# Qwiic_UV_Sensor_VEML6075.net
KiCad netlist of a schematic drawn in EAGLE
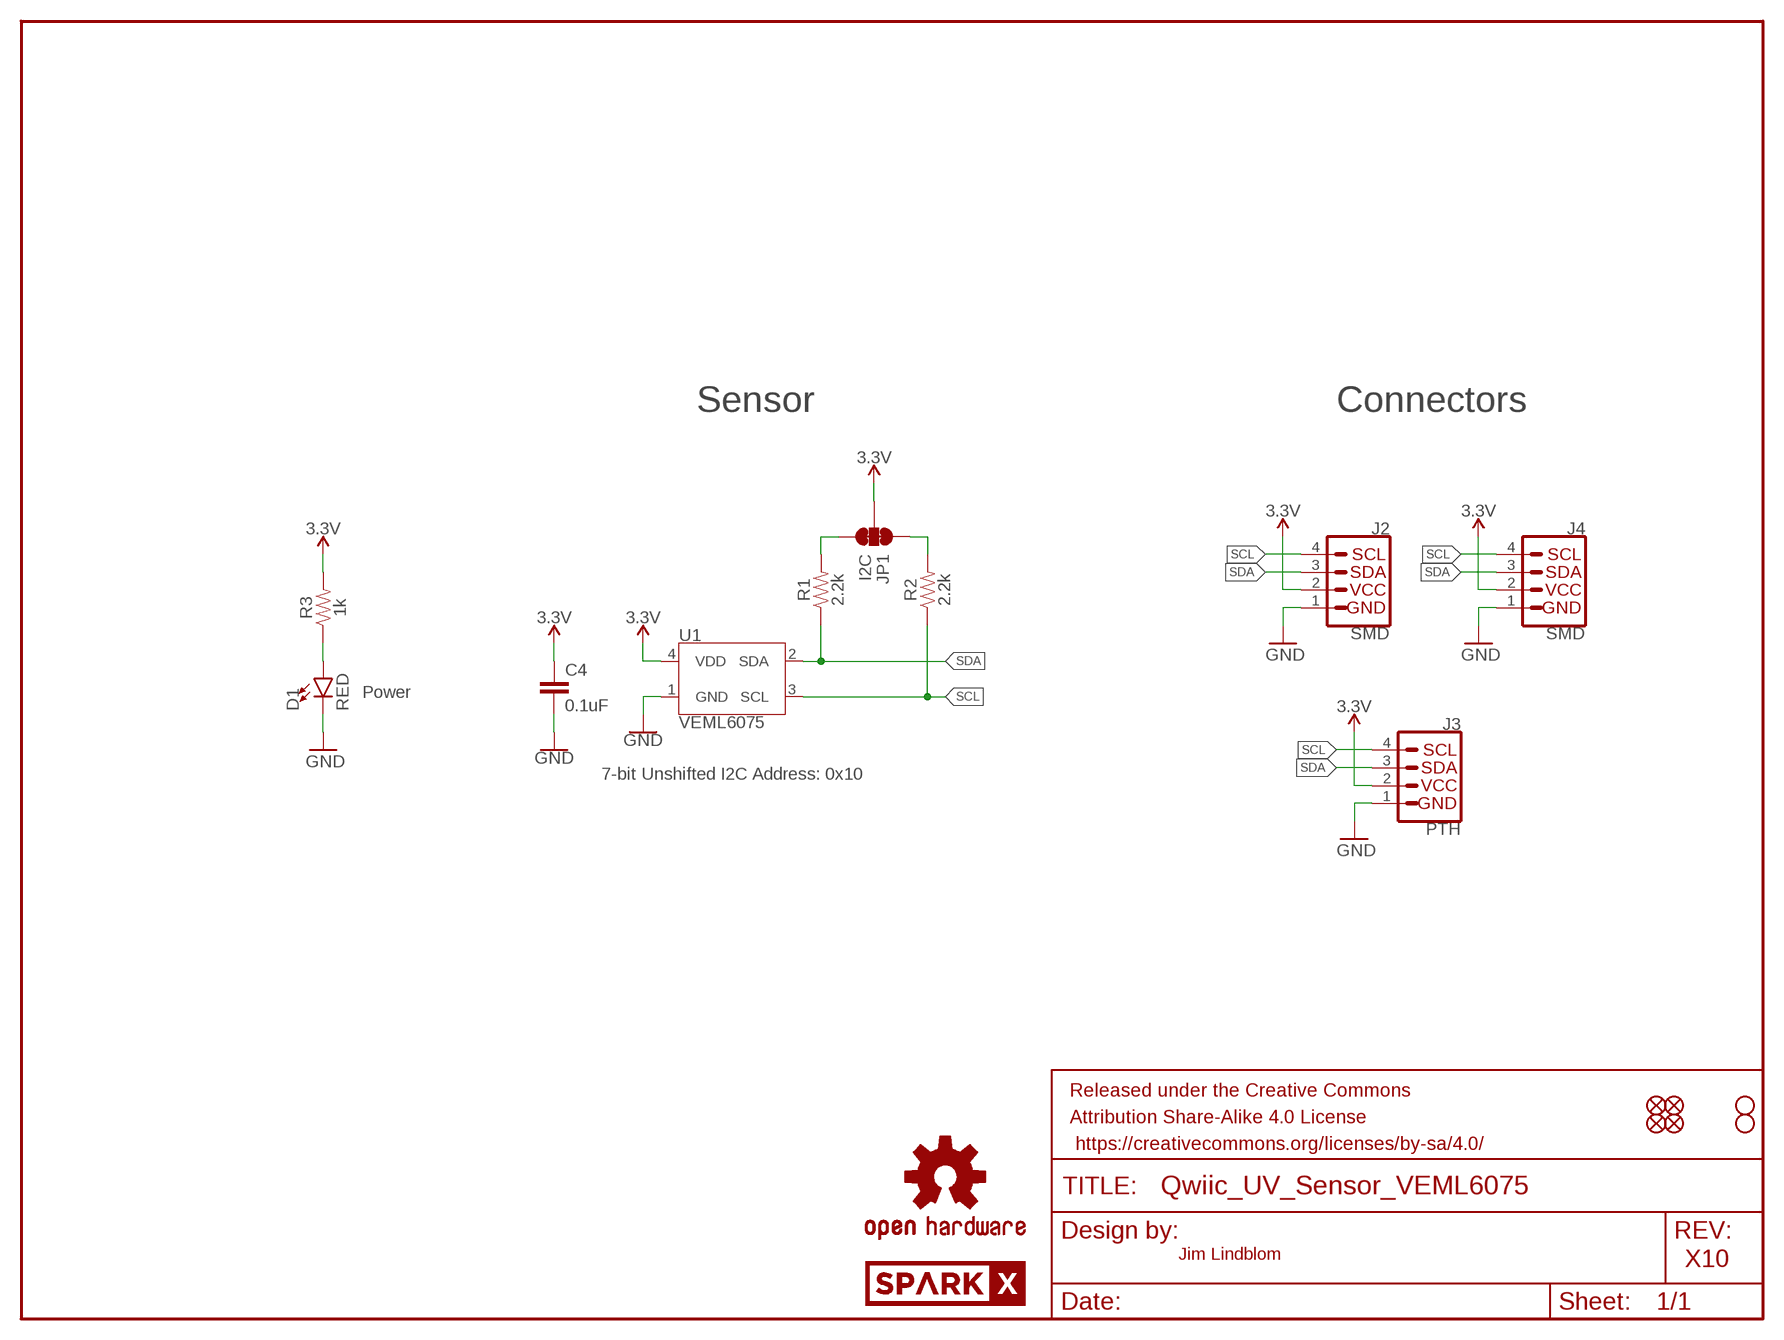
[diagram p0: schematic, sheet 1]

(export (version "E")
  (design (tool "Eeschema 10.0.6"))
  (components
    (comp (ref "C4")
      (value "0.1uF")
      (footprint "eagle-import:0603")
      (libsource (lib "eagle-import") (part "0.1UF-0603-25V-(+80/-20%)"))
    )
    (comp (ref "D1")
      (value "RED")
      (footprint "eagle-import:LED-0603")
      (libsource (lib "eagle-import") (part "LED-RED0603"))
    )
    (comp (ref "FRAME1")
      (value "FRAME-LETTER")
      (footprint "eagle-import:CREATIVE_COMMONS")
      (libsource (lib "eagle-import") (part "FRAME-LETTER"))
    )
    (comp (ref "J2")
      (value "SMD")
      (footprint "eagle-import:1X04_1MM_RA")
      (libsource (lib "eagle-import") (part "I2C_STANDARDJS-1MM"))
    )
    (comp (ref "J3")
      (value "PTH")
      (footprint "eagle-import:1X04_NO_SILK")
      (libsource (lib "eagle-import") (part "I2C_STANDARD_NO_SILK"))
    )
    (comp (ref "J4")
      (value "SMD")
      (footprint "eagle-import:1X04_1MM_RA")
      (libsource (lib "eagle-import") (part "I2C_STANDARDJS-1MM"))
    )
    (comp (ref "JP1")
      (value "I2C")
      (footprint "eagle-import:SMT-JUMPER_3_2-NC_TRACE_SILK")
      (libsource (lib "eagle-import") (part "JUMPER-SMT_3_2-NC_TRACE_SILK"))
    )
    (comp (ref "JP2")
      (value "FIDUCIALUFIDUCIAL")
      (footprint "eagle-import:MICRO-FIDUCIAL")
      (libsource (lib "eagle-import") (part "FIDUCIALUFIDUCIAL"))
    )
    (comp (ref "JP3")
      (value "STAND-OFF")
      (footprint "eagle-import:STAND-OFF")
      (libsource (lib "eagle-import") (part "STAND-OFF"))
    )
    (comp (ref "JP4")
      (value "STAND-OFF")
      (footprint "eagle-import:STAND-OFF")
      (libsource (lib "eagle-import") (part "STAND-OFF"))
    )
    (comp (ref "JP5")
      (value "FIDUCIALUFIDUCIAL")
      (footprint "eagle-import:MICRO-FIDUCIAL")
      (libsource (lib "eagle-import") (part "FIDUCIALUFIDUCIAL"))
    )
    (comp (ref "JP6")
      (value "FIDUCIALUFIDUCIAL")
      (footprint "eagle-import:MICRO-FIDUCIAL")
      (libsource (lib "eagle-import") (part "FIDUCIALUFIDUCIAL"))
    )
    (comp (ref "JP7")
      (value "FIDUCIALUFIDUCIAL")
      (footprint "eagle-import:MICRO-FIDUCIAL")
      (libsource (lib "eagle-import") (part "FIDUCIALUFIDUCIAL"))
    )
    (comp (ref "LOGO1")
      (value "OSHW-LOGOMINI")
      (footprint "eagle-import:OSHW-LOGO-MINI")
      (libsource (lib "eagle-import") (part "OSHW-LOGOMINI"))
    )
    (comp (ref "R1")
      (value "2.2k")
      (footprint "eagle-import:0603")
      (libsource (lib "eagle-import") (part "2.2KOHM-0603-1/10W-1%"))
    )
    (comp (ref "R2")
      (value "2.2k")
      (footprint "eagle-import:0603")
      (libsource (lib "eagle-import") (part "2.2KOHM-0603-1/10W-1%"))
    )
    (comp (ref "R3")
      (value "1k")
      (footprint "eagle-import:0603")
      (libsource (lib "eagle-import") (part "1KOHM-0603-1/10W-1%"))
    )
    (comp (ref "U$1")
      (value "SPARKX-LOGO4")
      (footprint "eagle-import:SPARKX-MEDIUM")
      (libsource (lib "eagle-import") (part "SPARKX-LOGO4"))
    )
    (comp (ref "U$2")
      (value "SPARKX-LOGO4")
      (footprint "eagle-import:SPARKX-MEDIUM")
      (libsource (lib "eagle-import") (part "SPARKX-LOGO4"))
    )
    (comp (ref "U1")
      (value "VEML6075")
      (footprint "eagle-import:VEML6075_A3OP")
      (libsource (lib "eagle-import") (part "VEML6075"))
    )
  )
  (nets
    (net (code "1") (name "3.3V") (class "Default")
      (node (ref "C4") (pin "1") (pinfunction "1_1") (pintype "passive"))
      (node (ref "J2") (pin "2") (pinfunction "VCC_2") (pintype "power_in"))
      (node (ref "J3") (pin "2") (pinfunction "VCC_2") (pintype "power_in"))
      (node (ref "J4") (pin "2") (pinfunction "VCC_2") (pintype "power_in"))
      (node (ref "JP1") (pin "2") (pinfunction "2_2") (pintype "passive"))
      (node (ref "R3") (pin "2") (pinfunction "2_2") (pintype "passive"))
      (node (ref "U1") (pin "4") (pinfunction "VDD_4") (pintype "bidirectional"))
    )
    (net (code "2") (name "GND") (class "Default")
      (node (ref "C4") (pin "2") (pinfunction "2_2") (pintype "passive"))
      (node (ref "D1") (pin "C") (pinfunction "C_C") (pintype "passive"))
      (node (ref "J2") (pin "1") (pinfunction "GND_1") (pintype "power_in"))
      (node (ref "J3") (pin "1") (pinfunction "GND_1") (pintype "power_in"))
      (node (ref "J4") (pin "1") (pinfunction "GND_1") (pintype "power_in"))
      (node (ref "U1") (pin "1") (pinfunction "GND_1") (pintype "bidirectional"))
    )
    (net (code "3") (name "Net-(D1-PadA)") (class "Default")
      (node (ref "D1") (pin "A") (pinfunction "A_A") (pintype "passive"))
      (node (ref "R3") (pin "1") (pinfunction "1_1") (pintype "passive"))
    )
    (net (code "4") (name "Net-(JP1-Pad1)") (class "Default")
      (node (ref "JP1") (pin "1") (pinfunction "1_1") (pintype "passive"))
      (node (ref "R2") (pin "2") (pinfunction "2_2") (pintype "passive"))
    )
    (net (code "5") (name "Net-(JP1-Pad3)") (class "Default")
      (node (ref "JP1") (pin "3") (pinfunction "3_3") (pintype "passive"))
      (node (ref "R1") (pin "2") (pinfunction "2_2") (pintype "passive"))
    )
    (net (code "6") (name "SCL") (class "Default")
      (node (ref "J2") (pin "4") (pinfunction "SCL_4") (pintype "passive"))
      (node (ref "J3") (pin "4") (pinfunction "SCL_4") (pintype "passive"))
      (node (ref "J4") (pin "4") (pinfunction "SCL_4") (pintype "passive"))
      (node (ref "R2") (pin "1") (pinfunction "1_1") (pintype "passive"))
      (node (ref "U1") (pin "3") (pinfunction "SCL_3") (pintype "bidirectional"))
    )
    (net (code "7") (name "SDA") (class "Default")
      (node (ref "J2") (pin "3") (pinfunction "SDA_3") (pintype "passive"))
      (node (ref "J3") (pin "3") (pinfunction "SDA_3") (pintype "passive"))
      (node (ref "J4") (pin "3") (pinfunction "SDA_3") (pintype "passive"))
      (node (ref "R1") (pin "1") (pinfunction "1_1") (pintype "passive"))
      (node (ref "U1") (pin "2") (pinfunction "SDA_2") (pintype "bidirectional"))
    )
  )
)
